# spi_lcd_v2.net
KiCad netlist of a schematic drawn in EAGLE
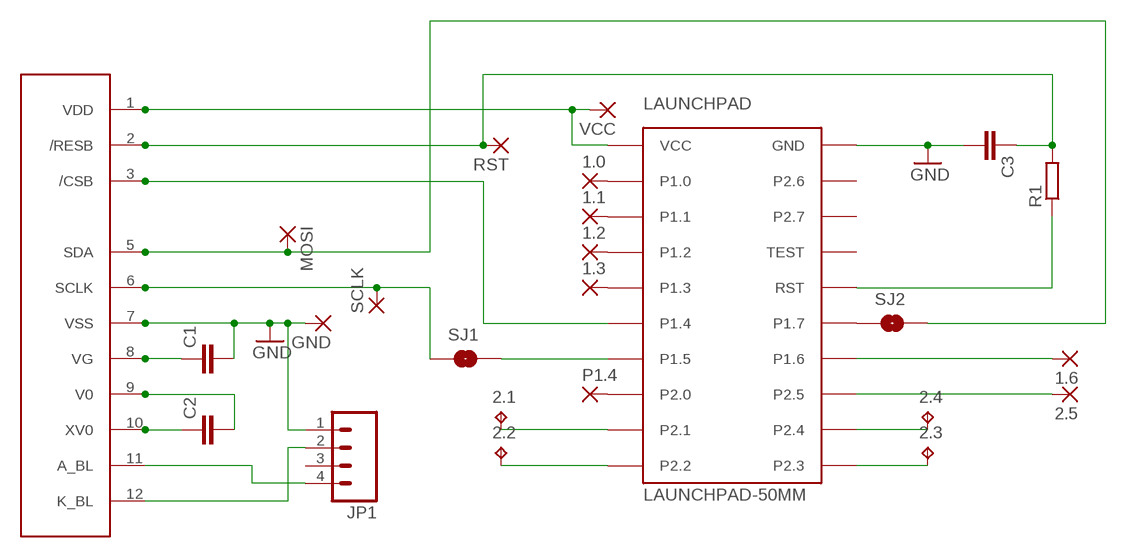
[diagram p0: schematic, sheet 1]

(export (version "E")
  (design (tool "Eeschema 10.0.6"))
  (components
    (comp (ref "1.0")
      (value "2,15/1,0")
      (footprint "eagle-import:2,15_1,0")
      (libsource (lib "eagle-import") (part "2,15/1,0"))
    )
    (comp (ref "1.1")
      (value "2,15/1,0")
      (footprint "eagle-import:2,15_1,0")
      (libsource (lib "eagle-import") (part "2,15/1,0"))
    )
    (comp (ref "1.2")
      (value "2,15/1,0")
      (footprint "eagle-import:2,15_1,0")
      (libsource (lib "eagle-import") (part "2,15/1,0"))
    )
    (comp (ref "1.3")
      (value "2,15/1,0")
      (footprint "eagle-import:2,15_1,0")
      (libsource (lib "eagle-import") (part "2,15/1,0"))
    )
    (comp (ref "1.6")
      (value "2,15/1,0")
      (footprint "eagle-import:2,15_1,0")
      (libsource (lib "eagle-import") (part "2,15/1,0"))
    )
    (comp (ref "2.1")
      (value "TPTP07R")
      (footprint "eagle-import:TP07R")
      (libsource (lib "eagle-import") (part "TPTP07R"))
    )
    (comp (ref "2.2")
      (value "TPTP07R")
      (footprint "eagle-import:TP07R")
      (libsource (lib "eagle-import") (part "TPTP07R"))
    )
    (comp (ref "2.3")
      (value "TPTP07R")
      (footprint "eagle-import:TP07R")
      (libsource (lib "eagle-import") (part "TPTP07R"))
    )
    (comp (ref "2.4")
      (value "TPTP07R")
      (footprint "eagle-import:TP07R")
      (libsource (lib "eagle-import") (part "TPTP07R"))
    )
    (comp (ref "2.5")
      (value "2,15/1,0")
      (footprint "eagle-import:2,15_1,0")
      (libsource (lib "eagle-import") (part "2,15/1,0"))
    )
    (comp (ref "C1")
      (value "CAP1206")
      (footprint "eagle-import:1206")
      (libsource (lib "eagle-import") (part "CAP1206"))
    )
    (comp (ref "C2")
      (value "CAP1206")
      (footprint "eagle-import:1206")
      (libsource (lib "eagle-import") (part "CAP1206"))
    )
    (comp (ref "C3")
      (value "CAP1206")
      (footprint "eagle-import:1206")
      (libsource (lib "eagle-import") (part "CAP1206"))
    )
    (comp (ref "GND")
      (value "2,15/1,0")
      (footprint "eagle-import:2,15_1,0")
      (libsource (lib "eagle-import") (part "2,15/1,0"))
    )
    (comp (ref "JP1")
      (value "M04PTH")
      (footprint "eagle-import:1X04")
      (libsource (lib "eagle-import") (part "M04PTH"))
    )
    (comp (ref "LAUNCHPAD")
      (value "LAUNCHPAD-50MM")
      (footprint "eagle-import:LAUNCHPAD-50MM")
      (libsource (lib "eagle-import") (part "LAUNCHPAD-50MM"))
    )
    (comp (ref "MOSI")
      (value "2,15/1,0")
      (footprint "eagle-import:2,15_1,0")
      (libsource (lib "eagle-import") (part "2,15/1,0"))
    )
    (comp (ref "P1.4")
      (value "2,15/1,0")
      (footprint "eagle-import:2,15_1,0")
      (libsource (lib "eagle-import") (part "2,15/1,0"))
    )
    (comp (ref "R1")
      (value "R-EU_R1206")
      (footprint "eagle-import:R1206")
      (libsource (lib "eagle-import") (part "R-EU_R1206"))
    )
    (comp (ref "RST")
      (value "2,15/1,0")
      (footprint "eagle-import:2,15_1,0")
      (libsource (lib "eagle-import") (part "2,15/1,0"))
    )
    (comp (ref "SCLK")
      (value "2,15/1,0")
      (footprint "eagle-import:2,15_1,0")
      (libsource (lib "eagle-import") (part "2,15/1,0"))
    )
    (comp (ref "SJ1")
      (value "SOLDERJUMPERTRACE")
      (footprint "eagle-import:SJ_2S-TRACE")
      (libsource (lib "eagle-import") (part "SOLDERJUMPERTRACE"))
    )
    (comp (ref "SJ2")
      (value "SOLDERJUMPERTRACE")
      (footprint "eagle-import:SJ_2S-TRACE")
      (libsource (lib "eagle-import") (part "SOLDERJUMPERTRACE"))
    )
    (comp (ref "U$1")
      (value "PE9665WRFPE9665WRF-WHOLE")
      (footprint "eagle-import:PE9665WRF")
      (libsource (lib "eagle-import") (part "PE9665WRFPE9665WRF-WHOLE"))
    )
    (comp (ref "VCC")
      (value "2,15/1,0")
      (footprint "eagle-import:2,15_1,0")
      (libsource (lib "eagle-import") (part "2,15/1,0"))
    )
  )
  (nets
    (net (code "1") (name "GND") (class "Default")
      (node (ref "C1") (pin "2") (pinfunction "2_2") (pintype "passive"))
      (node (ref "C3") (pin "2") (pinfunction "2_2") (pintype "passive"))
      (node (ref "GND") (pin "1") (pinfunction "P_1") (pintype "passive"))
      (node (ref "JP1") (pin "1") (pinfunction "1_1") (pintype "passive"))
      (node (ref "LAUNCHPAD") (pin "GND") (pinfunction "GND_GND") (pintype "power_in"))
      (node (ref "U$1") (pin "7") (pinfunction "VSS_7") (pintype "bidirectional"))
    )
    (net (code "2") (name "Net-(1.0-P)") (class "Default")
      (node (ref "1.0") (pin "1") (pinfunction "P_1") (pintype "passive"))
      (node (ref "LAUNCHPAD") (pin "P1.0") (pinfunction "P1.0_P1.0") (pintype "bidirectional"))
    )
    (net (code "3") (name "Net-(1.1-P)") (class "Default")
      (node (ref "1.1") (pin "1") (pinfunction "P_1") (pintype "passive"))
      (node (ref "LAUNCHPAD") (pin "P1.1") (pinfunction "P1.1_P1.1") (pintype "bidirectional"))
    )
    (net (code "4") (name "Net-(1.2-P)") (class "Default")
      (node (ref "1.2") (pin "1") (pinfunction "P_1") (pintype "passive"))
      (node (ref "LAUNCHPAD") (pin "P1.2") (pinfunction "P1.2_P1.2") (pintype "bidirectional"))
    )
    (net (code "5") (name "Net-(1.3-P)") (class "Default")
      (node (ref "1.3") (pin "1") (pinfunction "P_1") (pintype "passive"))
      (node (ref "LAUNCHPAD") (pin "P1.3") (pinfunction "P1.3_P1.3") (pintype "bidirectional"))
    )
    (net (code "6") (name "Net-(1.6-P)") (class "Default")
      (node (ref "1.6") (pin "1") (pinfunction "P_1") (pintype "passive"))
      (node (ref "LAUNCHPAD") (pin "P1.6") (pinfunction "P1.6_P1.6") (pintype "bidirectional"))
    )
    (net (code "7") (name "Net-(2.1-PadTP)") (class "Default")
      (node (ref "2.1") (pin "TP") (pinfunction "TP_TP") (pintype "input"))
      (node (ref "LAUNCHPAD") (pin "P2.1") (pinfunction "P2.1_P2.1") (pintype "bidirectional"))
    )
    (net (code "8") (name "Net-(2.2-PadTP)") (class "Default")
      (node (ref "2.2") (pin "TP") (pinfunction "TP_TP") (pintype "input"))
      (node (ref "LAUNCHPAD") (pin "P2.2") (pinfunction "P2.2_P2.2") (pintype "bidirectional"))
    )
    (net (code "9") (name "Net-(2.3-PadTP)") (class "Default")
      (node (ref "2.3") (pin "TP") (pinfunction "TP_TP") (pintype "input"))
      (node (ref "LAUNCHPAD") (pin "P2.3") (pinfunction "P2.3_P2.3") (pintype "bidirectional"))
    )
    (net (code "10") (name "Net-(2.4-PadTP)") (class "Default")
      (node (ref "2.4") (pin "TP") (pinfunction "TP_TP") (pintype "input"))
      (node (ref "LAUNCHPAD") (pin "P2.4") (pinfunction "P2.4_P2.4") (pintype "bidirectional"))
    )
    (net (code "11") (name "Net-(2.5-P)") (class "Default")
      (node (ref "2.5") (pin "1") (pinfunction "P_1") (pintype "passive"))
      (node (ref "LAUNCHPAD") (pin "P2.5") (pinfunction "P2.5_P2.5") (pintype "bidirectional"))
    )
    (net (code "12") (name "Net-(LAUNCHPAD-PadP1.5)") (class "Default")
      (node (ref "LAUNCHPAD") (pin "P1.5") (pinfunction "P1.5_P1.5") (pintype "bidirectional"))
      (node (ref "SJ1") (pin "2") (pinfunction "2_2") (pintype "passive"))
    )
    (net (code "13") (name "Net-(LAUNCHPAD-PadP1.7)") (class "Default")
      (node (ref "LAUNCHPAD") (pin "P1.7") (pinfunction "P1.7_P1.7") (pintype "bidirectional"))
      (node (ref "SJ2") (pin "1") (pinfunction "1_1") (pintype "passive"))
    )
    (net (code "14") (name "Net-(LAUNCHPAD-PadRST)") (class "Default")
      (node (ref "LAUNCHPAD") (pin "RST") (pinfunction "RST_RST") (pintype "bidirectional"))
      (node (ref "R1") (pin "1") (pinfunction "1_1") (pintype "passive"))
    )
    (net (code "15") (name "Net-(MOSI-P)") (class "Default")
      (node (ref "MOSI") (pin "1") (pinfunction "P_1") (pintype "passive"))
      (node (ref "SJ2") (pin "2") (pinfunction "2_2") (pintype "passive"))
      (node (ref "U$1") (pin "5") (pinfunction "SDA_5") (pintype "bidirectional"))
    )
    (net (code "16") (name "Net-(P1.4-P)") (class "Default")
      (node (ref "LAUNCHPAD") (pin "P2.0") (pinfunction "P2.0_P2.0") (pintype "bidirectional"))
      (node (ref "P1.4") (pin "1") (pinfunction "P_1") (pintype "passive"))
    )
    (net (code "17") (name "Net-(RST-P)") (class "Default")
      (node (ref "C3") (pin "1") (pinfunction "1_1") (pintype "passive"))
      (node (ref "R1") (pin "2") (pinfunction "2_2") (pintype "passive"))
      (node (ref "RST") (pin "1") (pinfunction "P_1") (pintype "passive"))
      (node (ref "U$1") (pin "2") (pinfunction "/RESB_2") (pintype "bidirectional"))
    )
    (net (code "18") (name "Net-(SCLK-P)") (class "Default")
      (node (ref "SCLK") (pin "1") (pinfunction "P_1") (pintype "passive"))
      (node (ref "SJ1") (pin "1") (pinfunction "1_1") (pintype "passive"))
      (node (ref "U$1") (pin "6") (pinfunction "SCLK_6") (pintype "bidirectional"))
    )
    (net (code "19") (name "Net-(U$1-A_BL)") (class "Default")
      (node (ref "JP1") (pin "4") (pinfunction "4_4") (pintype "passive"))
      (node (ref "U$1") (pin "11") (pinfunction "A_BL_11") (pintype "bidirectional"))
    )
    (net (code "20") (name "Net-(U$1-K_BL)") (class "Default")
      (node (ref "JP1") (pin "2") (pinfunction "2_2") (pintype "passive"))
      (node (ref "U$1") (pin "12") (pinfunction "K_BL_12") (pintype "bidirectional"))
    )
    (net (code "21") (name "Net-(U$1-V0)") (class "Default")
      (node (ref "C2") (pin "2") (pinfunction "2_2") (pintype "passive"))
      (node (ref "U$1") (pin "9") (pinfunction "V0_9") (pintype "bidirectional"))
    )
    (net (code "22") (name "Net-(U$1-VDD)") (class "Default")
      (node (ref "LAUNCHPAD") (pin "VCC") (pinfunction "VCC_VCC") (pintype "power_in"))
      (node (ref "U$1") (pin "1") (pinfunction "VDD_1") (pintype "bidirectional"))
      (node (ref "VCC") (pin "1") (pinfunction "P_1") (pintype "passive"))
    )
    (net (code "23") (name "Net-(U$1-VG)") (class "Default")
      (node (ref "C1") (pin "1") (pinfunction "1_1") (pintype "passive"))
      (node (ref "U$1") (pin "8") (pinfunction "VG_8") (pintype "bidirectional"))
    )
    (net (code "24") (name "Net-(U$1-XV0)") (class "Default")
      (node (ref "C2") (pin "1") (pinfunction "1_1") (pintype "passive"))
      (node (ref "U$1") (pin "10") (pinfunction "XV0_10") (pintype "bidirectional"))
    )
    (net (code "25") (name "Net-(U$1-{slash}CSB)") (class "Default")
      (node (ref "LAUNCHPAD") (pin "P1.4") (pinfunction "P1.4_P1.4") (pintype "bidirectional"))
      (node (ref "U$1") (pin "3") (pinfunction "/CSB_3") (pintype "bidirectional"))
    )
    (net (code "26") (name "unconnected-(JP1-Pad3)") (class "Default")
      (node (ref "JP1") (pin "3") (pinfunction "3_3") (pintype "passive"))
    )
    (net (code "27") (name "unconnected-(LAUNCHPAD-PadP2.6)") (class "Default")
      (node (ref "LAUNCHPAD") (pin "P2.6") (pinfunction "P2.6_P2.6") (pintype "bidirectional"))
    )
    (net (code "28") (name "unconnected-(LAUNCHPAD-PadP2.7)") (class "Default")
      (node (ref "LAUNCHPAD") (pin "P2.7") (pinfunction "P2.7_P2.7") (pintype "bidirectional"))
    )
    (net (code "29") (name "unconnected-(LAUNCHPAD-PadTEST)") (class "Default")
      (node (ref "LAUNCHPAD") (pin "TEST") (pinfunction "TEST_TEST") (pintype "bidirectional"))
    )
  )
)
